# Sheet1.net
KiCad netlist of a schematic drawn in Altium Designer
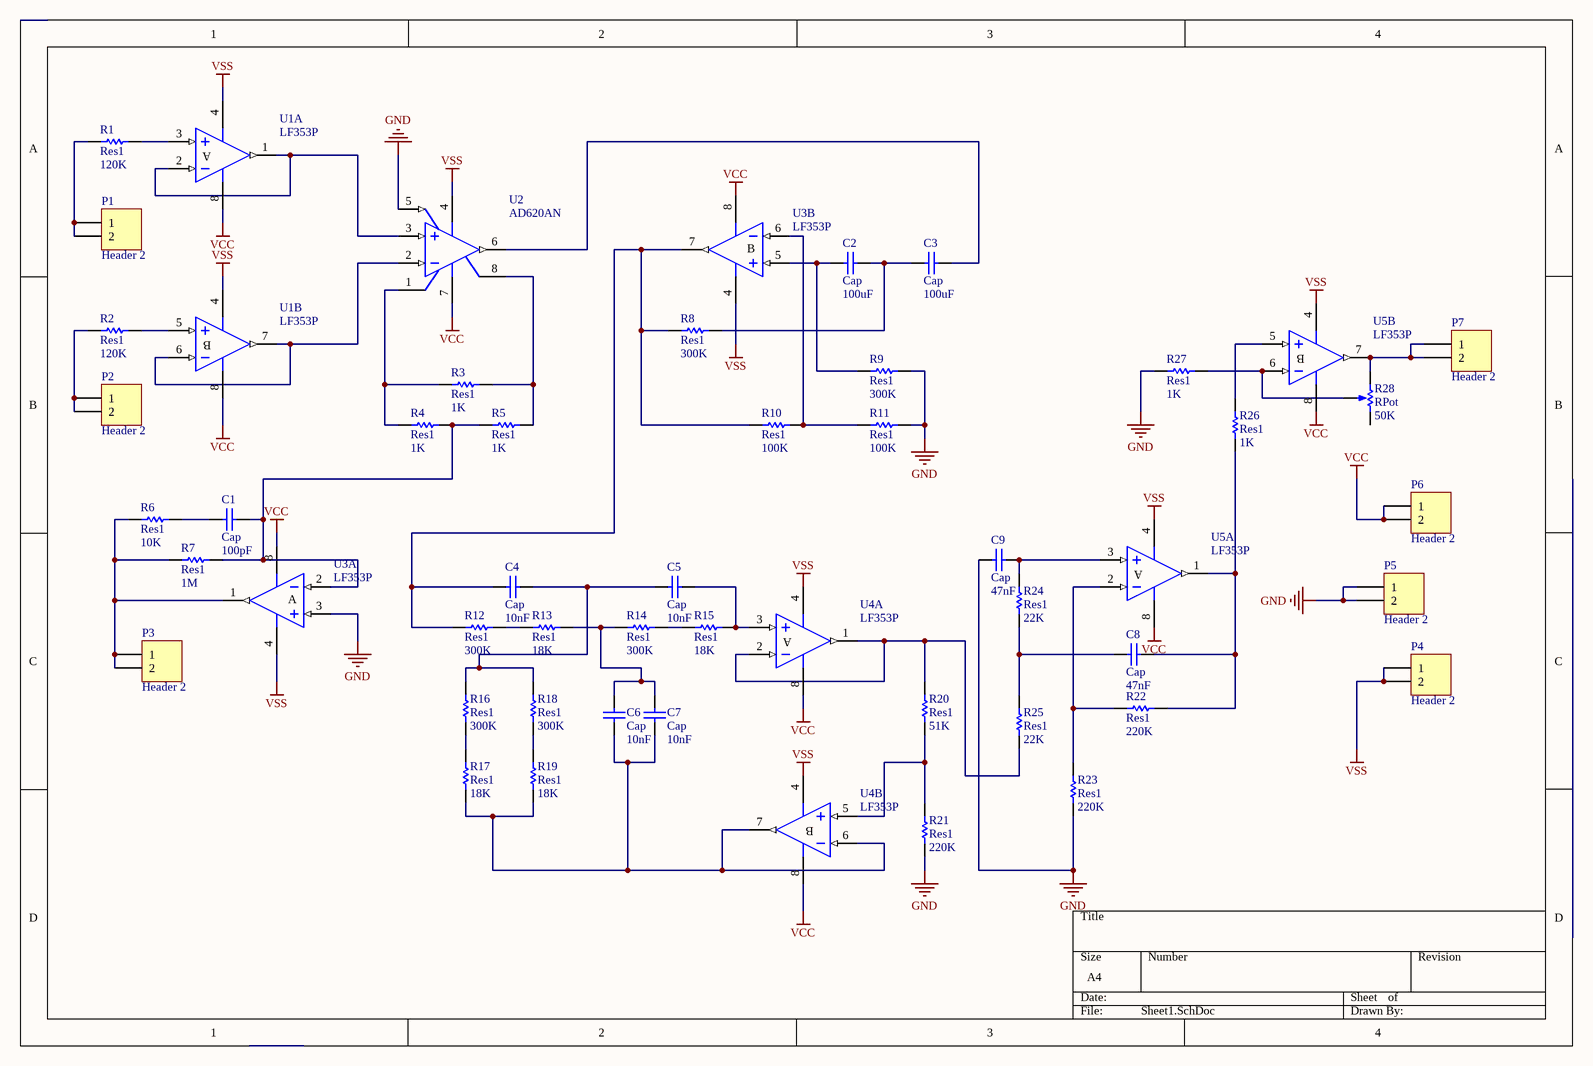
[diagram p0: Sheet1.SchDoc]

(export (version "E")
  (design (tool "Eeschema 10.0.6"))
  (components
    (comp (ref "C1")
      (value "Cap")
      (footprint "RAD-0.3")
      (description "Capacitor")
      (fields (field (name "ALTIUM_VALUE") "100pF") (field (name "PUBLISHER") "Altium Limited"))
      (libsource (lib "Miscellaneous Devices") (part "Cap"))
    )
    (comp (ref "C2")
      (value "Cap")
      (footprint "RAD-0.3")
      (description "Capacitor")
      (fields (field (name "ALTIUM_VALUE") "100uF") (field (name "PUBLISHER") "Altium Limited"))
      (libsource (lib "Miscellaneous Devices") (part "Cap"))
    )
    (comp (ref "C3")
      (value "Cap")
      (footprint "RAD-0.3")
      (description "Capacitor")
      (fields (field (name "ALTIUM_VALUE") "100uF") (field (name "PUBLISHER") "Altium Limited"))
      (libsource (lib "Miscellaneous Devices") (part "Cap"))
    )
    (comp (ref "C4")
      (value "Cap")
      (footprint "RAD-0.3")
      (description "Capacitor")
      (fields (field (name "ALTIUM_VALUE") "10nF") (field (name "PUBLISHER") "Altium Limited"))
      (libsource (lib "Miscellaneous Devices") (part "Cap"))
    )
    (comp (ref "C5")
      (value "Cap")
      (footprint "RAD-0.3")
      (description "Capacitor")
      (fields (field (name "ALTIUM_VALUE") "10nF") (field (name "PUBLISHER") "Altium Limited"))
      (libsource (lib "Miscellaneous Devices") (part "Cap"))
    )
    (comp (ref "C6")
      (value "Cap")
      (footprint "RAD-0.3")
      (description "Capacitor")
      (fields (field (name "ALTIUM_VALUE") "10nF") (field (name "PUBLISHER") "Altium Limited"))
      (libsource (lib "Miscellaneous Devices") (part "Cap"))
    )
    (comp (ref "C7")
      (value "Cap")
      (footprint "RAD-0.3")
      (description "Capacitor")
      (fields (field (name "ALTIUM_VALUE") "10nF") (field (name "PUBLISHER") "Altium Limited"))
      (libsource (lib "Miscellaneous Devices") (part "Cap"))
    )
    (comp (ref "C8")
      (value "Cap")
      (footprint "RAD-0.3")
      (description "Capacitor")
      (fields (field (name "ALTIUM_VALUE") "47nF") (field (name "PUBLISHER") "Altium Limited"))
      (libsource (lib "Miscellaneous Devices") (part "Cap"))
    )
    (comp (ref "C9")
      (value "Cap")
      (footprint "RAD-0.3")
      (description "Capacitor")
      (fields (field (name "ALTIUM_VALUE") "47nF") (field (name "PUBLISHER") "Altium Limited"))
      (libsource (lib "Miscellaneous Devices") (part "Cap"))
    )
    (comp (ref "P1")
      (value "Header 2")
      (footprint "HDR1X2")
      (description "Header, 2-Pin")
      (fields (field (name "PUBLISHER") "Altium Limited"))
      (libsource (lib "Miscellaneous Connectors") (part "Header 2"))
    )
    (comp (ref "P2")
      (value "Header 2")
      (footprint "HDR1X2")
      (description "Header, 2-Pin")
      (fields (field (name "PUBLISHER") "Altium Limited"))
      (libsource (lib "Miscellaneous Connectors") (part "Header 2"))
    )
    (comp (ref "P3")
      (value "Header 2")
      (footprint "HDR1X2")
      (description "Header, 2-Pin")
      (fields (field (name "PUBLISHER") "Altium Limited"))
      (libsource (lib "Miscellaneous Connectors") (part "Header 2"))
    )
    (comp (ref "P4")
      (value "Header 2")
      (footprint "HDR1X2")
      (description "Header, 2-Pin")
      (fields (field (name "PUBLISHER") "Altium Limited"))
      (libsource (lib "Miscellaneous Connectors") (part "Header 2"))
    )
    (comp (ref "P5")
      (value "Header 2")
      (footprint "HDR1X2")
      (description "Header, 2-Pin")
      (fields (field (name "PUBLISHER") "Altium Limited"))
      (libsource (lib "Miscellaneous Connectors") (part "Header 2"))
    )
    (comp (ref "P6")
      (value "Header 2")
      (footprint "HDR1X2")
      (description "Header, 2-Pin")
      (fields (field (name "PUBLISHER") "Altium Limited"))
      (libsource (lib "Miscellaneous Connectors") (part "Header 2"))
    )
    (comp (ref "P7")
      (value "Header 2")
      (footprint "HDR1X2")
      (description "Header, 2-Pin")
      (fields (field (name "PUBLISHER") "Altium Limited"))
      (libsource (lib "Miscellaneous Connectors") (part "Header 2"))
    )
    (comp (ref "R1")
      (value "Res1")
      (footprint "AXIAL-0.3")
      (description "Resistor")
      (fields (field (name "ALTIUM_VALUE") "120K") (field (name "PUBLISHER") "Altium Limited"))
      (libsource (lib "Miscellaneous Devices") (part "Res1"))
    )
    (comp (ref "R2")
      (value "Res1")
      (footprint "AXIAL-0.3")
      (description "Resistor")
      (fields (field (name "ALTIUM_VALUE") "120K") (field (name "PUBLISHER") "Altium Limited"))
      (libsource (lib "Miscellaneous Devices") (part "Res1"))
    )
    (comp (ref "R3")
      (value "Res1")
      (footprint "AXIAL-0.3")
      (description "Resistor")
      (fields (field (name "ALTIUM_VALUE") "1K") (field (name "PUBLISHER") "Altium Limited"))
      (libsource (lib "Miscellaneous Devices") (part "Res1"))
    )
    (comp (ref "R4")
      (value "Res1")
      (footprint "AXIAL-0.3")
      (description "Resistor")
      (fields (field (name "ALTIUM_VALUE") "1K") (field (name "PUBLISHER") "Altium Limited"))
      (libsource (lib "Miscellaneous Devices") (part "Res1"))
    )
    (comp (ref "R5")
      (value "Res1")
      (footprint "AXIAL-0.3")
      (description "Resistor")
      (fields (field (name "ALTIUM_VALUE") "1K") (field (name "PUBLISHER") "Altium Limited"))
      (libsource (lib "Miscellaneous Devices") (part "Res1"))
    )
    (comp (ref "R6")
      (value "Res1")
      (footprint "AXIAL-0.3")
      (description "Resistor")
      (fields (field (name "ALTIUM_VALUE") "10K") (field (name "PUBLISHER") "Altium Limited"))
      (libsource (lib "Miscellaneous Devices") (part "Res1"))
    )
    (comp (ref "R7")
      (value "Res1")
      (footprint "AXIAL-0.3")
      (description "Resistor")
      (fields (field (name "ALTIUM_VALUE") "1M") (field (name "PUBLISHER") "Altium Limited"))
      (libsource (lib "Miscellaneous Devices") (part "Res1"))
    )
    (comp (ref "R8")
      (value "Res1")
      (footprint "AXIAL-0.3")
      (description "Resistor")
      (fields (field (name "ALTIUM_VALUE") "300K") (field (name "PUBLISHER") "Altium Limited"))
      (libsource (lib "Miscellaneous Devices") (part "Res1"))
    )
    (comp (ref "R9")
      (value "Res1")
      (footprint "AXIAL-0.3")
      (description "Resistor")
      (fields (field (name "ALTIUM_VALUE") "300K") (field (name "PUBLISHER") "Altium Limited"))
      (libsource (lib "Miscellaneous Devices") (part "Res1"))
    )
    (comp (ref "R10")
      (value "Res1")
      (footprint "AXIAL-0.3")
      (description "Resistor")
      (fields (field (name "ALTIUM_VALUE") "100K") (field (name "PUBLISHER") "Altium Limited"))
      (libsource (lib "Miscellaneous Devices") (part "Res1"))
    )
    (comp (ref "R11")
      (value "Res1")
      (footprint "AXIAL-0.3")
      (description "Resistor")
      (fields (field (name "ALTIUM_VALUE") "100K") (field (name "PUBLISHER") "Altium Limited"))
      (libsource (lib "Miscellaneous Devices") (part "Res1"))
    )
    (comp (ref "R12")
      (value "Res1")
      (footprint "AXIAL-0.3")
      (description "Resistor")
      (fields (field (name "ALTIUM_VALUE") "300K") (field (name "PUBLISHER") "Altium Limited"))
      (libsource (lib "Miscellaneous Devices") (part "Res1"))
    )
    (comp (ref "R13")
      (value "Res1")
      (footprint "AXIAL-0.3")
      (description "Resistor")
      (fields (field (name "ALTIUM_VALUE") "18K") (field (name "PUBLISHER") "Altium Limited"))
      (libsource (lib "Miscellaneous Devices") (part "Res1"))
    )
    (comp (ref "R14")
      (value "Res1")
      (footprint "AXIAL-0.3")
      (description "Resistor")
      (fields (field (name "ALTIUM_VALUE") "300K") (field (name "PUBLISHER") "Altium Limited"))
      (libsource (lib "Miscellaneous Devices") (part "Res1"))
    )
    (comp (ref "R15")
      (value "Res1")
      (footprint "AXIAL-0.3")
      (description "Resistor")
      (fields (field (name "ALTIUM_VALUE") "18K") (field (name "PUBLISHER") "Altium Limited"))
      (libsource (lib "Miscellaneous Devices") (part "Res1"))
    )
    (comp (ref "R16")
      (value "Res1")
      (footprint "AXIAL-0.3")
      (description "Resistor")
      (fields (field (name "ALTIUM_VALUE") "300K") (field (name "PUBLISHER") "Altium Limited"))
      (libsource (lib "Miscellaneous Devices") (part "Res1"))
    )
    (comp (ref "R17")
      (value "Res1")
      (footprint "AXIAL-0.3")
      (description "Resistor")
      (fields (field (name "ALTIUM_VALUE") "18K") (field (name "PUBLISHER") "Altium Limited"))
      (libsource (lib "Miscellaneous Devices") (part "Res1"))
    )
    (comp (ref "R18")
      (value "Res1")
      (footprint "AXIAL-0.3")
      (description "Resistor")
      (fields (field (name "ALTIUM_VALUE") "300K") (field (name "PUBLISHER") "Altium Limited"))
      (libsource (lib "Miscellaneous Devices") (part "Res1"))
    )
    (comp (ref "R19")
      (value "Res1")
      (footprint "AXIAL-0.3")
      (description "Resistor")
      (fields (field (name "ALTIUM_VALUE") "18K") (field (name "PUBLISHER") "Altium Limited"))
      (libsource (lib "Miscellaneous Devices") (part "Res1"))
    )
    (comp (ref "R20")
      (value "Res1")
      (footprint "AXIAL-0.3")
      (description "Resistor")
      (fields (field (name "ALTIUM_VALUE") "51K") (field (name "PUBLISHER") "Altium Limited"))
      (libsource (lib "Miscellaneous Devices") (part "Res1"))
    )
    (comp (ref "R21")
      (value "Res1")
      (footprint "AXIAL-0.3")
      (description "Resistor")
      (fields (field (name "ALTIUM_VALUE") "220K") (field (name "PUBLISHER") "Altium Limited"))
      (libsource (lib "Miscellaneous Devices") (part "Res1"))
    )
    (comp (ref "R22")
      (value "Res1")
      (footprint "AXIAL-0.3")
      (description "Resistor")
      (fields (field (name "ALTIUM_VALUE") "220K") (field (name "PUBLISHER") "Altium Limited"))
      (libsource (lib "Miscellaneous Devices") (part "Res1"))
    )
    (comp (ref "R23")
      (value "Res1")
      (footprint "AXIAL-0.3")
      (description "Resistor")
      (fields (field (name "ALTIUM_VALUE") "220K") (field (name "PUBLISHER") "Altium Limited"))
      (libsource (lib "Miscellaneous Devices") (part "Res1"))
    )
    (comp (ref "R24")
      (value "Res1")
      (footprint "AXIAL-0.3")
      (description "Resistor")
      (fields (field (name "ALTIUM_VALUE") "22K") (field (name "PUBLISHER") "Altium Limited"))
      (libsource (lib "Miscellaneous Devices") (part "Res1"))
    )
    (comp (ref "R25")
      (value "Res1")
      (footprint "AXIAL-0.3")
      (description "Resistor")
      (fields (field (name "ALTIUM_VALUE") "22K") (field (name "PUBLISHER") "Altium Limited"))
      (libsource (lib "Miscellaneous Devices") (part "Res1"))
    )
    (comp (ref "R26")
      (value "Res1")
      (footprint "AXIAL-0.3")
      (description "Resistor")
      (fields (field (name "ALTIUM_VALUE") "1K") (field (name "PUBLISHER") "Altium Limited"))
      (libsource (lib "Miscellaneous Devices") (part "Res1"))
    )
    (comp (ref "R27")
      (value "Res1")
      (footprint "AXIAL-0.3")
      (description "Resistor")
      (fields (field (name "ALTIUM_VALUE") "1K") (field (name "PUBLISHER") "Altium Limited"))
      (libsource (lib "Miscellaneous Devices") (part "Res1"))
    )
    (comp (ref "R28")
      (value "RPot")
      (footprint "VR5")
      (description "Potentiometer")
      (fields (field (name "ALTIUM_VALUE") "50K") (field (name "PUBLISHER") "Altium Limited"))
      (libsource (lib "Miscellaneous Devices") (part "RPot"))
    )
    (comp (ref "U1")
      (value "LF353P")
      (footprint "P008")
      (description "Dual Operational Amplifier")
      (fields (field (name "PUBLISHER") "Altium Limited"))
      (libsource (lib "TI Operational Amplifier") (part "LF353P"))
    )
    (comp (ref "U2")
      (value "AD620AN")
      (footprint "N-8")
      (description "Low-Cost, Low-Power Instrumentation Amplifier")
      (fields (field (name "PUBLISHER") "Altium Limited"))
      (libsource (lib "AD Instrumentation Amplifier") (part "AD620AN"))
    )
    (comp (ref "U3")
      (value "LF353P")
      (footprint "P008")
      (description "Dual Operational Amplifier")
      (fields (field (name "PUBLISHER") "Altium Limited"))
      (libsource (lib "TI Operational Amplifier") (part "LF353P"))
    )
    (comp (ref "U4")
      (value "LF353P")
      (footprint "P008")
      (description "Dual Operational Amplifier")
      (fields (field (name "PUBLISHER") "Altium Limited"))
      (libsource (lib "TI Operational Amplifier") (part "LF353P"))
    )
    (comp (ref "U5")
      (value "LF353P")
      (footprint "P008")
      (description "Dual Operational Amplifier")
      (fields (field (name "PUBLISHER") "Altium Limited"))
      (libsource (lib "TI Operational Amplifier") (part "LF353P"))
    )
  )
  (nets
    (net (code "1") (name "GND") (class "Default")
      (node (ref "C9") (pin "1") (pinfunction "1_1") (pintype "passive"))
      (node (ref "P5") (pin "1") (pinfunction "1_1") (pintype "passive"))
      (node (ref "P5") (pin "2") (pinfunction "2_2") (pintype "passive"))
      (node (ref "R11") (pin "2") (pinfunction "2_2") (pintype "passive"))
      (node (ref "R21") (pin "1") (pinfunction "1_1") (pintype "passive"))
      (node (ref "R23") (pin "1") (pinfunction "1_1") (pintype "passive"))
      (node (ref "R27") (pin "1") (pinfunction "1_1") (pintype "passive"))
      (node (ref "R9") (pin "2") (pinfunction "2_2") (pintype "passive"))
      (node (ref "U2") (pin "5") (pinfunction "REF_5") (pintype "input"))
      (node (ref "U3") (pin "3") (pinfunction "IN+_3") (pintype "input"))
    )
    (net (code "2") (name "Net-(C1-Pad1)") (class "Default")
      (node (ref "C1") (pin "1") (pinfunction "1_1") (pintype "passive"))
      (node (ref "R6") (pin "2") (pinfunction "2_2") (pintype "passive"))
    )
    (net (code "3") (name "Net-(C2-Pad2)") (class "Default")
      (node (ref "C2") (pin "2") (pinfunction "2_2") (pintype "passive"))
      (node (ref "C3") (pin "1") (pinfunction "1_1") (pintype "passive"))
      (node (ref "R8") (pin "2") (pinfunction "2_2") (pintype "passive"))
    )
    (net (code "4") (name "Net-(C4-Pad2)") (class "Default")
      (node (ref "C4") (pin "2") (pinfunction "2_2") (pintype "passive"))
      (node (ref "C5") (pin "1") (pinfunction "1_1") (pintype "passive"))
      (node (ref "R16") (pin "2") (pinfunction "2_2") (pintype "passive"))
      (node (ref "R18") (pin "2") (pinfunction "2_2") (pintype "passive"))
    )
    (net (code "5") (name "Net-(C6-Pad2)") (class "Default")
      (node (ref "C6") (pin "2") (pinfunction "2_2") (pintype "passive"))
      (node (ref "C7") (pin "2") (pinfunction "2_2") (pintype "passive"))
      (node (ref "R13") (pin "2") (pinfunction "2_2") (pintype "passive"))
      (node (ref "R14") (pin "1") (pinfunction "1_1") (pintype "passive"))
    )
    (net (code "6") (name "Net-(C8-Pad1)") (class "Default")
      (node (ref "C8") (pin "1") (pinfunction "1_1") (pintype "passive"))
      (node (ref "R24") (pin "1") (pinfunction "1_1") (pintype "passive"))
      (node (ref "R25") (pin "2") (pinfunction "2_2") (pintype "passive"))
    )
    (net (code "7") (name "Net-(P1-Pad1)") (class "Default")
      (node (ref "P1") (pin "1") (pinfunction "1_1") (pintype "passive"))
      (node (ref "P1") (pin "2") (pinfunction "2_2") (pintype "passive"))
      (node (ref "R1") (pin "1") (pinfunction "1_1") (pintype "passive"))
    )
    (net (code "8") (name "Net-(P2-Pad1)") (class "Default")
      (node (ref "P2") (pin "1") (pinfunction "1_1") (pintype "passive"))
      (node (ref "P2") (pin "2") (pinfunction "2_2") (pintype "passive"))
      (node (ref "R2") (pin "1") (pinfunction "1_1") (pintype "passive"))
    )
    (net (code "9") (name "Net-(R3-Pad1)") (class "Default")
      (node (ref "R3") (pin "1") (pinfunction "1_1") (pintype "passive"))
      (node (ref "R4") (pin "1") (pinfunction "1_1") (pintype "passive"))
      (node (ref "U2") (pin "1") (pinfunction "RG_1") (pintype "passive"))
    )
    (net (code "10") (name "Net-(R3-Pad2)") (class "Default")
      (node (ref "R3") (pin "2") (pinfunction "2_2") (pintype "passive"))
      (node (ref "R5") (pin "2") (pinfunction "2_2") (pintype "passive"))
      (node (ref "U2") (pin "8") (pinfunction "RG_8") (pintype "passive"))
    )
    (net (code "11") (name "Net-(R12-Pad2)") (class "Default")
      (node (ref "R12") (pin "2") (pinfunction "2_2") (pintype "passive"))
      (node (ref "R13") (pin "1") (pinfunction "1_1") (pintype "passive"))
    )
    (net (code "12") (name "Net-(R14-Pad2)") (class "Default")
      (node (ref "R14") (pin "2") (pinfunction "2_2") (pintype "passive"))
      (node (ref "R15") (pin "1") (pinfunction "1_1") (pintype "passive"))
    )
    (net (code "13") (name "Net-(R16-Pad1)") (class "Default")
      (node (ref "R16") (pin "1") (pinfunction "1_1") (pintype "passive"))
      (node (ref "R17") (pin "2") (pinfunction "2_2") (pintype "passive"))
    )
    (net (code "14") (name "Net-(R18-Pad1)") (class "Default")
      (node (ref "R18") (pin "1") (pinfunction "1_1") (pintype "passive"))
      (node (ref "R19") (pin "2") (pinfunction "2_2") (pintype "passive"))
    )
    (net (code "15") (name "Net-(R28-TAP)") (class "Default")
      (node (ref "R27") (pin "2") (pinfunction "2_2") (pintype "passive"))
      (node (ref "R28") (pin "3") (pinfunction "TAP_3") (pintype "passive"))
      (node (ref "U5") (pin "6") (pinfunction "IN-_6") (pintype "input"))
    )
    (net (code "16") (name "Net-(R28-TOP)") (class "Default")
      (node (ref "P7") (pin "1") (pinfunction "1_1") (pintype "passive"))
      (node (ref "P7") (pin "2") (pinfunction "2_2") (pintype "passive"))
      (node (ref "R28") (pin "1") (pinfunction "TOP_1") (pintype "passive"))
      (node (ref "U5") (pin "7") (pinfunction "OUT_7") (pintype "output"))
    )
    (net (code "17") (name "Net-(U1A-IN+)") (class "Default")
      (node (ref "R1") (pin "2") (pinfunction "2_2") (pintype "passive"))
      (node (ref "U1") (pin "3") (pinfunction "IN+_3") (pintype "input"))
    )
    (net (code "18") (name "Net-(U1A-IN-)") (class "Default")
      (node (ref "U1") (pin "1") (pinfunction "OUT_1") (pintype "output"))
      (node (ref "U1") (pin "2") (pinfunction "IN-_2") (pintype "input"))
      (node (ref "U2") (pin "3") (pinfunction "+IN_3") (pintype "input"))
    )
    (net (code "19") (name "Net-(U1B-IN+)") (class "Default")
      (node (ref "R2") (pin "2") (pinfunction "2_2") (pintype "passive"))
      (node (ref "U1") (pin "5") (pinfunction "IN+_5") (pintype "input"))
    )
    (net (code "20") (name "Net-(U1B-IN-)") (class "Default")
      (node (ref "U1") (pin "6") (pinfunction "IN-_6") (pintype "input"))
      (node (ref "U1") (pin "7") (pinfunction "OUT_7") (pintype "output"))
      (node (ref "U2") (pin "2") (pinfunction "-IN_2") (pintype "input"))
    )
    (net (code "21") (name "Net-(U2-OUT)") (class "Default")
      (node (ref "C3") (pin "2") (pinfunction "2_2") (pintype "passive"))
      (node (ref "U2") (pin "6") (pinfunction "OUT_6") (pintype "output"))
    )
    (net (code "22") (name "Net-(U3A-IN-)") (class "Default")
      (node (ref "C1") (pin "2") (pinfunction "2_2") (pintype "passive"))
      (node (ref "R4") (pin "2") (pinfunction "2_2") (pintype "passive"))
      (node (ref "R5") (pin "1") (pinfunction "1_1") (pintype "passive"))
      (node (ref "R7") (pin "2") (pinfunction "2_2") (pintype "passive"))
      (node (ref "U3") (pin "2") (pinfunction "IN-_2") (pintype "input"))
    )
    (net (code "23") (name "Net-(U3A-OUT)") (class "Default")
      (node (ref "P3") (pin "1") (pinfunction "1_1") (pintype "passive"))
      (node (ref "P3") (pin "2") (pinfunction "2_2") (pintype "passive"))
      (node (ref "R6") (pin "1") (pinfunction "1_1") (pintype "passive"))
      (node (ref "R7") (pin "1") (pinfunction "1_1") (pintype "passive"))
      (node (ref "U3") (pin "1") (pinfunction "OUT_1") (pintype "output"))
    )
    (net (code "24") (name "Net-(U3B-IN+)") (class "Default")
      (node (ref "C2") (pin "1") (pinfunction "1_1") (pintype "passive"))
      (node (ref "R9") (pin "1") (pinfunction "1_1") (pintype "passive"))
      (node (ref "U3") (pin "5") (pinfunction "IN+_5") (pintype "input"))
    )
    (net (code "25") (name "Net-(U3B-IN-)") (class "Default")
      (node (ref "R10") (pin "2") (pinfunction "2_2") (pintype "passive"))
      (node (ref "R11") (pin "1") (pinfunction "1_1") (pintype "passive"))
      (node (ref "U3") (pin "6") (pinfunction "IN-_6") (pintype "input"))
    )
    (net (code "26") (name "Net-(U3B-OUT)") (class "Default")
      (node (ref "C4") (pin "1") (pinfunction "1_1") (pintype "passive"))
      (node (ref "R10") (pin "1") (pinfunction "1_1") (pintype "passive"))
      (node (ref "R12") (pin "1") (pinfunction "1_1") (pintype "passive"))
      (node (ref "R8") (pin "1") (pinfunction "1_1") (pintype "passive"))
      (node (ref "U3") (pin "7") (pinfunction "OUT_7") (pintype "output"))
    )
    (net (code "27") (name "Net-(U4A-IN+)") (class "Default")
      (node (ref "C5") (pin "2") (pinfunction "2_2") (pintype "passive"))
      (node (ref "R15") (pin "2") (pinfunction "2_2") (pintype "passive"))
      (node (ref "U4") (pin "3") (pinfunction "IN+_3") (pintype "input"))
    )
    (net (code "28") (name "Net-(U4A-IN-)") (class "Default")
      (node (ref "R20") (pin "2") (pinfunction "2_2") (pintype "passive"))
      (node (ref "R25") (pin "1") (pinfunction "1_1") (pintype "passive"))
      (node (ref "U4") (pin "1") (pinfunction "OUT_1") (pintype "output"))
      (node (ref "U4") (pin "2") (pinfunction "IN-_2") (pintype "input"))
    )
    (net (code "29") (name "Net-(U4B-IN+)") (class "Default")
      (node (ref "R20") (pin "1") (pinfunction "1_1") (pintype "passive"))
      (node (ref "R21") (pin "2") (pinfunction "2_2") (pintype "passive"))
      (node (ref "U4") (pin "5") (pinfunction "IN+_5") (pintype "input"))
    )
    (net (code "30") (name "Net-(U4B-IN-)") (class "Default")
      (node (ref "C6") (pin "1") (pinfunction "1_1") (pintype "passive"))
      (node (ref "C7") (pin "1") (pinfunction "1_1") (pintype "passive"))
      (node (ref "R17") (pin "1") (pinfunction "1_1") (pintype "passive"))
      (node (ref "R19") (pin "1") (pinfunction "1_1") (pintype "passive"))
      (node (ref "U4") (pin "6") (pinfunction "IN-_6") (pintype "input"))
      (node (ref "U4") (pin "7") (pinfunction "OUT_7") (pintype "output"))
    )
    (net (code "31") (name "Net-(U5A-IN+)") (class "Default")
      (node (ref "C9") (pin "2") (pinfunction "2_2") (pintype "passive"))
      (node (ref "R24") (pin "2") (pinfunction "2_2") (pintype "passive"))
      (node (ref "U5") (pin "3") (pinfunction "IN+_3") (pintype "input"))
    )
    (net (code "32") (name "Net-(U5A-IN-)") (class "Default")
      (node (ref "R22") (pin "1") (pinfunction "1_1") (pintype "passive"))
      (node (ref "R23") (pin "2") (pinfunction "2_2") (pintype "passive"))
      (node (ref "U5") (pin "2") (pinfunction "IN-_2") (pintype "input"))
    )
    (net (code "33") (name "Net-(U5A-OUT)") (class "Default")
      (node (ref "C8") (pin "2") (pinfunction "2_2") (pintype "passive"))
      (node (ref "R22") (pin "2") (pinfunction "2_2") (pintype "passive"))
      (node (ref "R26") (pin "1") (pinfunction "1_1") (pintype "passive"))
      (node (ref "U5") (pin "1") (pinfunction "OUT_1") (pintype "output"))
    )
    (net (code "34") (name "Net-(U5B-IN+)") (class "Default")
      (node (ref "R26") (pin "2") (pinfunction "2_2") (pintype "passive"))
      (node (ref "U5") (pin "5") (pinfunction "IN+_5") (pintype "input"))
    )
    (net (code "35") (name "VCC") (class "Default")
      (node (ref "P6") (pin "1") (pinfunction "1_1") (pintype "passive"))
      (node (ref "P6") (pin "2") (pinfunction "2_2") (pintype "passive"))
      (node (ref "U1") (pin "8") (pinfunction "V+_8") (pintype "power_in"))
      (node (ref "U2") (pin "7") (pinfunction "V+_7") (pintype "power_in"))
      (node (ref "U3") (pin "8") (pinfunction "V+_8") (pintype "power_in"))
      (node (ref "U4") (pin "8") (pinfunction "V+_8") (pintype "power_in"))
      (node (ref "U5") (pin "8") (pinfunction "V+_8") (pintype "power_in"))
    )
    (net (code "36") (name "VSS") (class "Default")
      (node (ref "P4") (pin "1") (pinfunction "1_1") (pintype "passive"))
      (node (ref "P4") (pin "2") (pinfunction "2_2") (pintype "passive"))
      (node (ref "U1") (pin "4") (pinfunction "V-_4") (pintype "power_in"))
      (node (ref "U2") (pin "4") (pinfunction "V-_4") (pintype "power_in"))
      (node (ref "U3") (pin "4") (pinfunction "V-_4") (pintype "power_in"))
      (node (ref "U4") (pin "4") (pinfunction "V-_4") (pintype "power_in"))
      (node (ref "U5") (pin "4") (pinfunction "V-_4") (pintype "power_in"))
    )
    (net (code "37") (name "unconnected-(R28-BOT-Pad2)") (class "Default")
      (node (ref "R28") (pin "2") (pinfunction "BOT_2") (pintype "passive"))
    )
  )
)
